# ProPrj___2024-03-13_07-09-23_2025-06-12.net
KiCad netlist of a schematic drawn in EasyEDA Pro
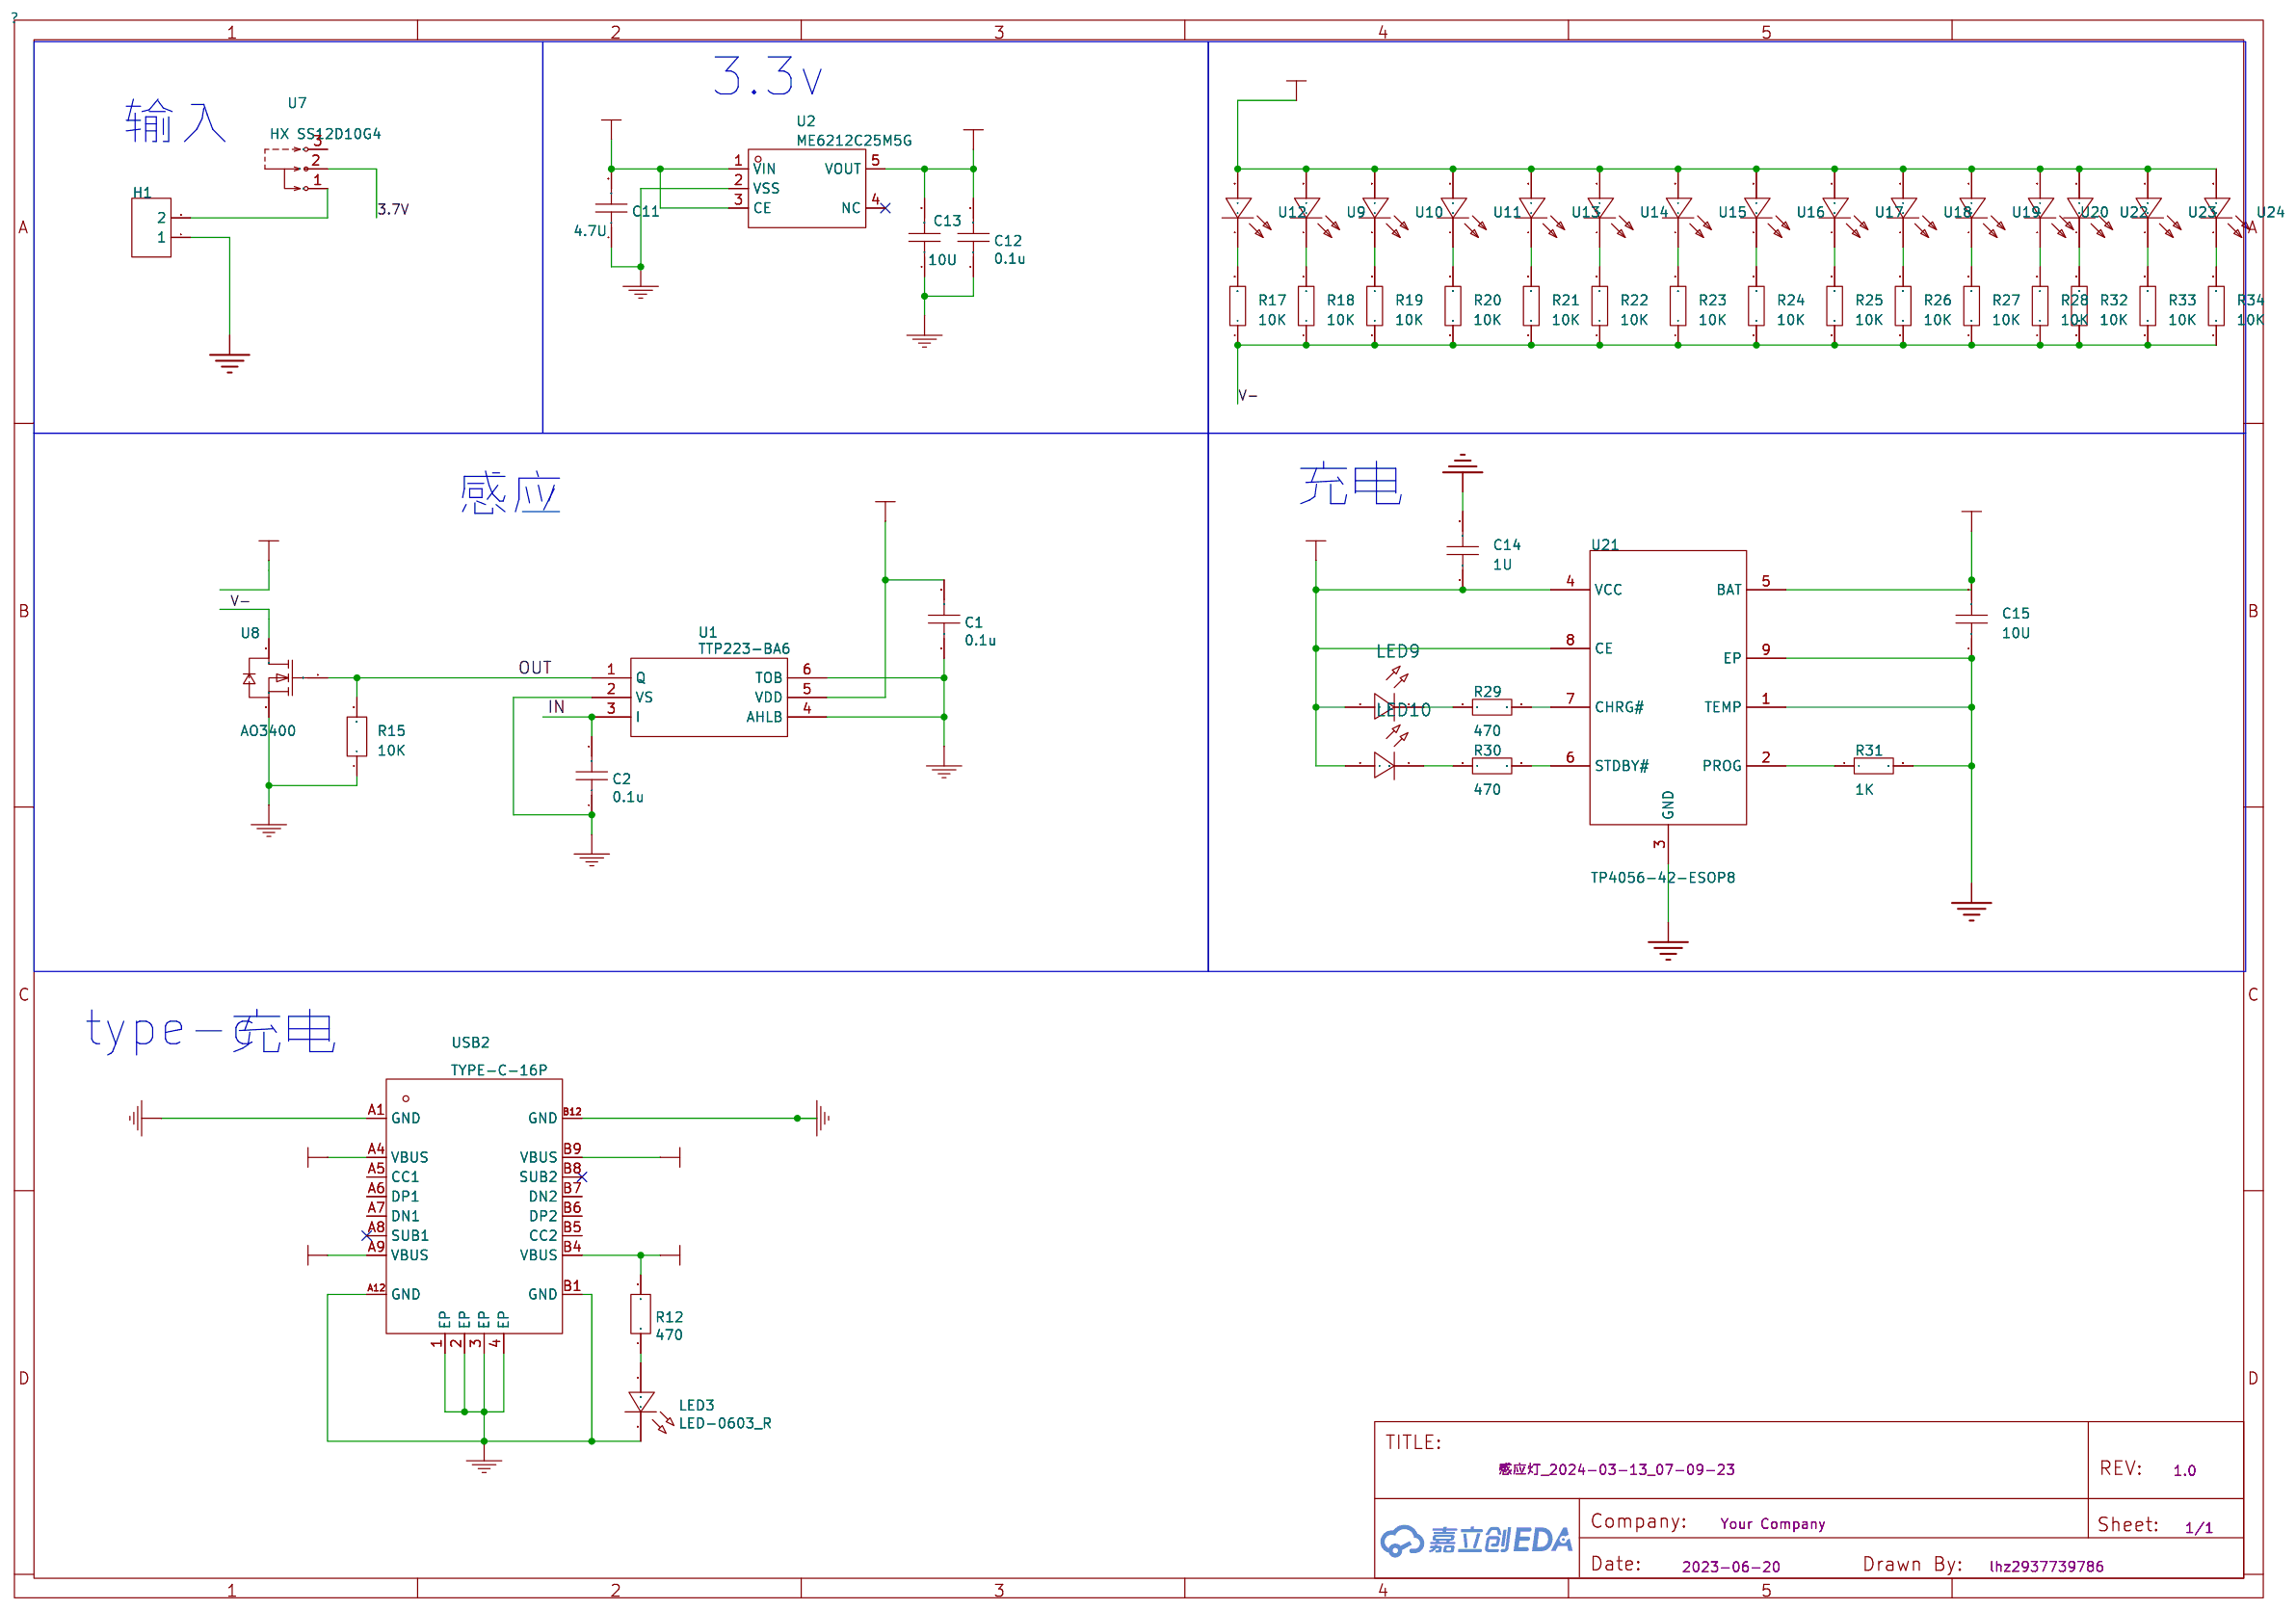
[diagram p0: schematic sheet]

(export (version "E")
  (design (tool "Eeschema 10.0.6"))
  (components
    (comp (ref "C1")
      (value "0.1u")
      (footprint "easyedapro:footprint_1e94")
      (libsource (lib "easyedapro") (part "0.1u"))
    )
    (comp (ref "C2")
      (value "0.1u")
      (footprint "easyedapro:footprint_1e94")
      (libsource (lib "easyedapro") (part "0.1u"))
    )
    (comp (ref "C11")
      (value "4.7U")
      (footprint "easyedapro:footprint_d063")
      (libsource (lib "easyedapro") (part "4.7U"))
    )
    (comp (ref "C12")
      (value "0.1u")
      (footprint "easyedapro:footprint_d063")
      (libsource (lib "easyedapro") (part "0.1u"))
    )
    (comp (ref "C13")
      (value "10U")
      (footprint "easyedapro:footprint_d063")
      (libsource (lib "easyedapro") (part "10U"))
    )
    (comp (ref "C14")
      (value "1U")
      (footprint "easyedapro:C0603")
      (libsource (lib "easyedapro") (part "CapAcitance"))
    )
    (comp (ref "C15")
      (value "10U")
      (footprint "easyedapro:C0603")
      (libsource (lib "easyedapro") (part "CapAcitance"))
    )
    (comp (ref "H1")
      (value "~")
      (footprint "easyedapro:HDR-TH_2P-P2.54-V-F")
      (libsource (lib "easyedapro") (part "Header-Female-2.54_1x2"))
    )
    (comp (ref "LED3")
      (value "LED-0603_R")
      (footprint "easyedapro:footprint_1210")
      (fields
        (field (name "Manufacturer Part") "19-217/R6C-AL1M2VY/3T")
        (field (name "Manufacturer") "EVERLIGHT(台湾亿光)")
      )
      (libsource (lib "easyedapro") (part "LED-0603_R"))
    )
    (comp (ref "LED9")
      (value "~")
      (footprint "easyedapro:LED_0603")
      (libsource (lib "easyedapro") (part "LED_R"))
    )
    (comp (ref "LED10")
      (value "~")
      (footprint "easyedapro:LED_0603")
      (libsource (lib "easyedapro") (part "LED_R"))
    )
    (comp (ref "R12")
      (value "470")
      (footprint "easyedapro:footprint_1dde")
      (libsource (lib "easyedapro") (part "470"))
    )
    (comp (ref "R15")
      (value "10K")
      (footprint "easyedapro:footprint_4dfc")
      (libsource (lib "easyedapro") (part "10K"))
    )
    (comp (ref "R17") (value "10K") (footprint "easyedapro:R0805") (libsource (lib "easyedapro") (part "电阻")))
    (comp (ref "R18") (value "10K") (footprint "easyedapro:R0805") (libsource (lib "easyedapro") (part "电阻")))
    (comp (ref "R19") (value "10K") (footprint "easyedapro:R0805") (libsource (lib "easyedapro") (part "电阻")))
    (comp (ref "R20") (value "10K") (footprint "easyedapro:R0805") (libsource (lib "easyedapro") (part "电阻")))
    (comp (ref "R21") (value "10K") (footprint "easyedapro:R0805") (libsource (lib "easyedapro") (part "电阻")))
    (comp (ref "R22") (value "10K") (footprint "easyedapro:R0805") (libsource (lib "easyedapro") (part "电阻")))
    (comp (ref "R23") (value "10K") (footprint "easyedapro:R0805") (libsource (lib "easyedapro") (part "电阻")))
    (comp (ref "R24") (value "10K") (footprint "easyedapro:R0805") (libsource (lib "easyedapro") (part "电阻")))
    (comp (ref "R25") (value "10K") (footprint "easyedapro:R0805") (libsource (lib "easyedapro") (part "电阻")))
    (comp (ref "R26") (value "10K") (footprint "easyedapro:R0805") (libsource (lib "easyedapro") (part "电阻")))
    (comp (ref "R27") (value "10K") (footprint "easyedapro:R0805") (libsource (lib "easyedapro") (part "电阻")))
    (comp (ref "R28") (value "10K") (footprint "easyedapro:R0805") (libsource (lib "easyedapro") (part "电阻")))
    (comp (ref "R29") (value "470") (footprint "easyedapro:R0805") (libsource (lib "easyedapro") (part "电阻")))
    (comp (ref "R30") (value "470") (footprint "easyedapro:R0805") (libsource (lib "easyedapro") (part "电阻")))
    (comp (ref "R31") (value "1K") (footprint "easyedapro:R0805") (libsource (lib "easyedapro") (part "电阻")))
    (comp (ref "R32") (value "10K") (footprint "easyedapro:R0805") (libsource (lib "easyedapro") (part "电阻")))
    (comp (ref "R33") (value "10K") (footprint "easyedapro:R0805") (libsource (lib "easyedapro") (part "电阻")))
    (comp (ref "R34") (value "10K") (footprint "easyedapro:R0805") (libsource (lib "easyedapro") (part "电阻")))
    (comp (ref "U1")
      (value "TTP223-BA6")
      (footprint "easyedapro:footprint_07fe")
      (libsource (lib "easyedapro") (part "TTP223-BA6"))
    )
    (comp (ref "U2")
      (value "ME6212C25M5G")
      (footprint "easyedapro:footprint_203e")
      (fields (field (name "Manufacturer") "MICRONE(南京微盟)"))
      (libsource (lib "easyedapro") (part "ME6212C25M5G"))
    )
    (comp (ref "U7")
      (value "HX SS12D10G4")
      (footprint "easyedapro:footprint_a0a6")
      (fields (field (name "Manufacturer") "hanxia(韩下)"))
      (libsource (lib "easyedapro") (part "HX SS12D10G4"))
    )
    (comp (ref "U8")
      (value "AO3400")
      (footprint "easyedapro:footprint_8e82")
      (fields (field (name "Manufacturer") "ElecSuper(静芯微）"))
      (libsource (lib "easyedapro") (part "AO3400"))
    )
    (comp (ref "U9")
      (value "~")
      (footprint "easyedapro:led-smd_l3.5-w2.8-r-fd-white")
      (fields (field (name "Manufacturer Part") "LED2835"))
      (libsource (lib "easyedapro") (part "led2835"))
    )
    (comp (ref "U10")
      (value "~")
      (footprint "easyedapro:led-smd_l3.5-w2.8-r-fd-white")
      (fields (field (name "Manufacturer Part") "LED2835"))
      (libsource (lib "easyedapro") (part "led2835"))
    )
    (comp (ref "U11")
      (value "~")
      (footprint "easyedapro:led-smd_l3.5-w2.8-r-fd-white")
      (fields (field (name "Manufacturer Part") "LED2835"))
      (libsource (lib "easyedapro") (part "led2835"))
    )
    (comp (ref "U12")
      (value "~")
      (footprint "easyedapro:led-smd_l3.5-w2.8-r-fd-white")
      (fields (field (name "Manufacturer Part") "LED2835"))
      (libsource (lib "easyedapro") (part "led2835"))
    )
    (comp (ref "U13")
      (value "~")
      (footprint "easyedapro:led-smd_l3.5-w2.8-r-fd-white")
      (fields (field (name "Manufacturer Part") "LED2835"))
      (libsource (lib "easyedapro") (part "led2835"))
    )
    (comp (ref "U14")
      (value "~")
      (footprint "easyedapro:led-smd_l3.5-w2.8-r-fd-white")
      (fields (field (name "Manufacturer Part") "LED2835"))
      (libsource (lib "easyedapro") (part "led2835"))
    )
    (comp (ref "U15")
      (value "~")
      (footprint "easyedapro:led-smd_l3.5-w2.8-r-fd-white")
      (fields (field (name "Manufacturer Part") "LED2835"))
      (libsource (lib "easyedapro") (part "led2835"))
    )
    (comp (ref "U16")
      (value "~")
      (footprint "easyedapro:led-smd_l3.5-w2.8-r-fd-white")
      (fields (field (name "Manufacturer Part") "LED2835"))
      (libsource (lib "easyedapro") (part "led2835"))
    )
    (comp (ref "U17")
      (value "~")
      (footprint "easyedapro:led-smd_l3.5-w2.8-r-fd-white")
      (fields (field (name "Manufacturer Part") "LED2835"))
      (libsource (lib "easyedapro") (part "led2835"))
    )
    (comp (ref "U18")
      (value "~")
      (footprint "easyedapro:led-smd_l3.5-w2.8-r-fd-white")
      (fields (field (name "Manufacturer Part") "LED2835"))
      (libsource (lib "easyedapro") (part "led2835"))
    )
    (comp (ref "U19")
      (value "~")
      (footprint "easyedapro:led-smd_l3.5-w2.8-r-fd-white")
      (fields (field (name "Manufacturer Part") "LED2835"))
      (libsource (lib "easyedapro") (part "led2835"))
    )
    (comp (ref "U20")
      (value "~")
      (footprint "easyedapro:led-smd_l3.5-w2.8-r-fd-white")
      (fields (field (name "Manufacturer Part") "LED2835"))
      (libsource (lib "easyedapro") (part "led2835"))
    )
    (comp (ref "U21")
      (value "TP4056-42-ESOP8")
      (footprint "easyedapro:ESOP-8_L4.9-W3.9-P1.27-LS6.0-BL-EP")
      (description "充电电池的类型:-;电池单元组数:-;最大充电电流:-;充满的电池组电压:-;最大供应电压:-;")
      (fields (field (name "Manufacturer") "TOPPOWER(南京拓微)"))
      (libsource (lib "easyedapro") (part "TP4056"))
    )
    (comp (ref "U22")
      (value "~")
      (footprint "easyedapro:led-smd_l3.5-w2.8-r-fd-white")
      (fields (field (name "Manufacturer Part") "LED2835"))
      (libsource (lib "easyedapro") (part "led2835"))
    )
    (comp (ref "U23")
      (value "~")
      (footprint "easyedapro:led-smd_l3.5-w2.8-r-fd-white")
      (fields (field (name "Manufacturer Part") "LED2835"))
      (libsource (lib "easyedapro") (part "led2835"))
    )
    (comp (ref "U24")
      (value "~")
      (footprint "easyedapro:led-smd_l3.5-w2.8-r-fd-white")
      (fields (field (name "Manufacturer Part") "LED2835"))
      (libsource (lib "easyedapro") (part "led2835"))
    )
    (comp (ref "USB2")
      (value "TYPE-C-16P")
      (footprint "easyedapro:footprint_feef")
      (fields
        (field (name "Manufacturer Part") "KH-TYPE-C-16P")
        (field (name "Manufacturer") "Shenzhen Kinghelm Elec")
      )
      (libsource (lib "easyedapro") (part "TYPE-C-16P"))
    )
  )
  (nets
    (net (code "1") (name "/IN") (class "Default")
      (node (ref "C2") (pin "2") (pinfunction "2_2") (pintype "unspecified"))
      (node (ref "U1") (pin "3") (pinfunction "I_3") (pintype "unspecified"))
    )
    (net (code "2") (name "/OUT") (class "Default")
      (node (ref "R15") (pin "2") (pinfunction "2_2") (pintype "unspecified"))
      (node (ref "U1") (pin "1") (pinfunction "Q_1") (pintype "unspecified"))
      (node (ref "U8") (pin "1") (pinfunction "G_1") (pintype "unspecified"))
    )
    (net (code "3") (name "/V-") (class "Default")
      (node (ref "R17") (pin "1") (pinfunction "1_1") (pintype "input"))
      (node (ref "R18") (pin "1") (pinfunction "1_1") (pintype "input"))
      (node (ref "R19") (pin "1") (pinfunction "1_1") (pintype "input"))
      (node (ref "R20") (pin "1") (pinfunction "1_1") (pintype "input"))
      (node (ref "R21") (pin "1") (pinfunction "1_1") (pintype "input"))
      (node (ref "R22") (pin "1") (pinfunction "1_1") (pintype "input"))
      (node (ref "R23") (pin "1") (pinfunction "1_1") (pintype "input"))
      (node (ref "R24") (pin "1") (pinfunction "1_1") (pintype "input"))
      (node (ref "R25") (pin "1") (pinfunction "1_1") (pintype "input"))
      (node (ref "R26") (pin "1") (pinfunction "1_1") (pintype "input"))
      (node (ref "R27") (pin "1") (pinfunction "1_1") (pintype "input"))
      (node (ref "R28") (pin "1") (pinfunction "1_1") (pintype "input"))
      (node (ref "R32") (pin "1") (pinfunction "1_1") (pintype "input"))
      (node (ref "R33") (pin "1") (pinfunction "1_1") (pintype "input"))
      (node (ref "R34") (pin "1") (pinfunction "1_1") (pintype "input"))
      (node (ref "U8") (pin "3") (pinfunction "D_3") (pintype "unspecified"))
    )
    (net (code "4") (name "3.3V") (class "Default")
      (node (ref "C1") (pin "2") (pinfunction "2_2") (pintype "unspecified"))
      (node (ref "C12") (pin "2") (pinfunction "2_2") (pintype "unspecified"))
      (node (ref "C13") (pin "2") (pinfunction "2_2") (pintype "unspecified"))
      (node (ref "U1") (pin "5") (pinfunction "VDD_5") (pintype "unspecified"))
      (node (ref "U2") (pin "5") (pinfunction "VOUT_5") (pintype "unspecified"))
    )
    (net (code "5") (name "3.7V") (class "Default")
      (node (ref "C11") (pin "2") (pinfunction "2_2") (pintype "unspecified"))
      (node (ref "C15") (pin "2") (pinfunction "2_2") (pintype "input"))
      (node (ref "U10") (pin "2") (pinfunction "A_2") (pintype "input"))
      (node (ref "U11") (pin "2") (pinfunction "A_2") (pintype "input"))
      (node (ref "U12") (pin "2") (pinfunction "A_2") (pintype "input"))
      (node (ref "U13") (pin "2") (pinfunction "A_2") (pintype "input"))
      (node (ref "U14") (pin "2") (pinfunction "A_2") (pintype "input"))
      (node (ref "U15") (pin "2") (pinfunction "A_2") (pintype "input"))
      (node (ref "U16") (pin "2") (pinfunction "A_2") (pintype "input"))
      (node (ref "U17") (pin "2") (pinfunction "A_2") (pintype "input"))
      (node (ref "U18") (pin "2") (pinfunction "A_2") (pintype "input"))
      (node (ref "U19") (pin "2") (pinfunction "A_2") (pintype "input"))
      (node (ref "U2") (pin "1") (pinfunction "VIN_1") (pintype "unspecified"))
      (node (ref "U2") (pin "3") (pinfunction "CE_3") (pintype "unspecified"))
      (node (ref "U20") (pin "2") (pinfunction "A_2") (pintype "input"))
      (node (ref "U21") (pin "5") (pinfunction "BAT_5") (pintype "input"))
      (node (ref "U22") (pin "2") (pinfunction "A_2") (pintype "input"))
      (node (ref "U23") (pin "2") (pinfunction "A_2") (pintype "input"))
      (node (ref "U24") (pin "2") (pinfunction "A_2") (pintype "input"))
      (node (ref "U7") (pin "2") (pinfunction "2_2") (pintype "unspecified"))
      (node (ref "U9") (pin "2") (pinfunction "A_2") (pintype "input"))
    )
    (net (code "6") (name "5V") (class "Default")
      (node (ref "C14") (pin "1") (pinfunction "1_1") (pintype "input"))
      (node (ref "LED10") (pin "2") (pinfunction "A_2") (pintype "input"))
      (node (ref "LED9") (pin "2") (pinfunction "A_2") (pintype "input"))
      (node (ref "R12") (pin "2") (pinfunction "2_2") (pintype "unspecified"))
      (node (ref "U21") (pin "4") (pinfunction "VCC_4") (pintype "input"))
      (node (ref "U21") (pin "8") (pinfunction "CE_8") (pintype "input"))
      (node (ref "USB2") (pin "A4") (pinfunction "VBUS_A4") (pintype "unspecified"))
      (node (ref "USB2") (pin "A9") (pinfunction "VBUS_A9") (pintype "unspecified"))
      (node (ref "USB2") (pin "B4") (pinfunction "VBUS_B4") (pintype "unspecified"))
      (node (ref "USB2") (pin "B9") (pinfunction "VBUS_B9") (pintype "unspecified"))
    )
    (net (code "7") (name "GND") (class "Default")
      (node (ref "C1") (pin "1") (pinfunction "1_1") (pintype "unspecified"))
      (node (ref "C11") (pin "1") (pinfunction "1_1") (pintype "unspecified"))
      (node (ref "C12") (pin "1") (pinfunction "1_1") (pintype "unspecified"))
      (node (ref "C13") (pin "1") (pinfunction "1_1") (pintype "unspecified"))
      (node (ref "C14") (pin "2") (pinfunction "2_2") (pintype "input"))
      (node (ref "C15") (pin "1") (pinfunction "1_1") (pintype "input"))
      (node (ref "C2") (pin "1") (pinfunction "1_1") (pintype "unspecified"))
      (node (ref "H1") (pin "1") (pinfunction "1_1") (pintype "input"))
      (node (ref "LED3") (pin "2") (pinfunction "2_2") (pintype "unspecified"))
      (node (ref "R15") (pin "1") (pinfunction "1_1") (pintype "unspecified"))
      (node (ref "R31") (pin "2") (pinfunction "2_2") (pintype "input"))
      (node (ref "U1") (pin "2") (pinfunction "VS_2") (pintype "unspecified"))
      (node (ref "U1") (pin "4") (pinfunction "AHLB_4") (pintype "unspecified"))
      (node (ref "U1") (pin "6") (pinfunction "TOB_6") (pintype "unspecified"))
      (node (ref "U2") (pin "2") (pinfunction "VSS_2") (pintype "unspecified"))
      (node (ref "U21") (pin "1") (pinfunction "TEMP_1") (pintype "input"))
      (node (ref "U21") (pin "3") (pinfunction "GND_3") (pintype "input"))
      (node (ref "U21") (pin "9") (pinfunction "EP_9") (pintype "input"))
      (node (ref "U8") (pin "2") (pinfunction "S_2") (pintype "unspecified"))
      (node (ref "USB2") (pin "1") (pinfunction "EP_1") (pintype "unspecified"))
      (node (ref "USB2") (pin "2") (pinfunction "EP_2") (pintype "unspecified"))
      (node (ref "USB2") (pin "3") (pinfunction "EP_3") (pintype "unspecified"))
      (node (ref "USB2") (pin "4") (pinfunction "EP_4") (pintype "unspecified"))
      (node (ref "USB2") (pin "A1") (pinfunction "GND_A1") (pintype "unspecified"))
      (node (ref "USB2") (pin "A12") (pinfunction "GND_A12") (pintype "unspecified"))
      (node (ref "USB2") (pin "B1") (pinfunction "GND_B1") (pintype "unspecified"))
      (node (ref "USB2") (pin "B12") (pinfunction "GND_B12") (pintype "unspecified"))
    )
    (net (code "8") (name "Net-(H1-Pad2)") (class "Default")
      (node (ref "H1") (pin "2") (pinfunction "2_2") (pintype "input"))
      (node (ref "U7") (pin "1") (pinfunction "1_1") (pintype "unspecified"))
    )
    (net (code "9") (name "Net-(LED3-Pad1)") (class "Default")
      (node (ref "LED3") (pin "1") (pinfunction "1_1") (pintype "unspecified"))
      (node (ref "R12") (pin "1") (pinfunction "1_1") (pintype "unspecified"))
    )
    (net (code "10") (name "Net-(LED9-C)") (class "Default")
      (node (ref "LED9") (pin "1") (pinfunction "C_1") (pintype "input"))
      (node (ref "R29") (pin "1") (pinfunction "1_1") (pintype "input"))
    )
    (net (code "11") (name "Net-(LED10-C)") (class "Default")
      (node (ref "LED10") (pin "1") (pinfunction "C_1") (pintype "input"))
      (node (ref "R30") (pin "1") (pinfunction "1_1") (pintype "input"))
    )
    (net (code "12") (name "Net-(U9-K)") (class "Default")
      (node (ref "R18") (pin "2") (pinfunction "2_2") (pintype "input"))
      (node (ref "U9") (pin "1") (pinfunction "K_1") (pintype "input"))
    )
    (net (code "13") (name "Net-(U10-K)") (class "Default")
      (node (ref "R19") (pin "2") (pinfunction "2_2") (pintype "input"))
      (node (ref "U10") (pin "1") (pinfunction "K_1") (pintype "input"))
    )
    (net (code "14") (name "Net-(U11-K)") (class "Default")
      (node (ref "R20") (pin "2") (pinfunction "2_2") (pintype "input"))
      (node (ref "U11") (pin "1") (pinfunction "K_1") (pintype "input"))
    )
    (net (code "15") (name "Net-(U12-K)") (class "Default")
      (node (ref "R17") (pin "2") (pinfunction "2_2") (pintype "input"))
      (node (ref "U12") (pin "1") (pinfunction "K_1") (pintype "input"))
    )
    (net (code "16") (name "Net-(U13-K)") (class "Default")
      (node (ref "R21") (pin "2") (pinfunction "2_2") (pintype "input"))
      (node (ref "U13") (pin "1") (pinfunction "K_1") (pintype "input"))
    )
    (net (code "17") (name "Net-(U14-K)") (class "Default")
      (node (ref "R22") (pin "2") (pinfunction "2_2") (pintype "input"))
      (node (ref "U14") (pin "1") (pinfunction "K_1") (pintype "input"))
    )
    (net (code "18") (name "Net-(U15-K)") (class "Default")
      (node (ref "R23") (pin "2") (pinfunction "2_2") (pintype "input"))
      (node (ref "U15") (pin "1") (pinfunction "K_1") (pintype "input"))
    )
    (net (code "19") (name "Net-(U16-K)") (class "Default")
      (node (ref "R24") (pin "2") (pinfunction "2_2") (pintype "input"))
      (node (ref "U16") (pin "1") (pinfunction "K_1") (pintype "input"))
    )
    (net (code "20") (name "Net-(U17-K)") (class "Default")
      (node (ref "R25") (pin "2") (pinfunction "2_2") (pintype "input"))
      (node (ref "U17") (pin "1") (pinfunction "K_1") (pintype "input"))
    )
    (net (code "21") (name "Net-(U18-K)") (class "Default")
      (node (ref "R26") (pin "2") (pinfunction "2_2") (pintype "input"))
      (node (ref "U18") (pin "1") (pinfunction "K_1") (pintype "input"))
    )
    (net (code "22") (name "Net-(U19-K)") (class "Default")
      (node (ref "R27") (pin "2") (pinfunction "2_2") (pintype "input"))
      (node (ref "U19") (pin "1") (pinfunction "K_1") (pintype "input"))
    )
    (net (code "23") (name "Net-(U20-K)") (class "Default")
      (node (ref "R28") (pin "2") (pinfunction "2_2") (pintype "input"))
      (node (ref "U20") (pin "1") (pinfunction "K_1") (pintype "input"))
    )
    (net (code "24") (name "Net-(U21-CHRG#)") (class "Default")
      (node (ref "R29") (pin "2") (pinfunction "2_2") (pintype "input"))
      (node (ref "U21") (pin "7") (pinfunction "CHRG#_7") (pintype "input"))
    )
    (net (code "25") (name "Net-(U21-PROG)") (class "Default")
      (node (ref "R31") (pin "1") (pinfunction "1_1") (pintype "input"))
      (node (ref "U21") (pin "2") (pinfunction "PROG_2") (pintype "input"))
    )
    (net (code "26") (name "Net-(U21-STDBY#)") (class "Default")
      (node (ref "R30") (pin "2") (pinfunction "2_2") (pintype "input"))
      (node (ref "U21") (pin "6") (pinfunction "STDBY#_6") (pintype "input"))
    )
    (net (code "27") (name "Net-(U22-K)") (class "Default")
      (node (ref "R32") (pin "2") (pinfunction "2_2") (pintype "input"))
      (node (ref "U22") (pin "1") (pinfunction "K_1") (pintype "input"))
    )
    (net (code "28") (name "Net-(U23-K)") (class "Default")
      (node (ref "R33") (pin "2") (pinfunction "2_2") (pintype "input"))
      (node (ref "U23") (pin "1") (pinfunction "K_1") (pintype "input"))
    )
    (net (code "29") (name "Net-(U24-K)") (class "Default")
      (node (ref "R34") (pin "2") (pinfunction "2_2") (pintype "input"))
      (node (ref "U24") (pin "1") (pinfunction "K_1") (pintype "input"))
    )
    (net (code "30") (name "unconnected-(U2-NC-Pad4)") (class "Default")
      (node (ref "U2") (pin "4") (pinfunction "NC_4") (pintype "unspecified+no_connect"))
    )
    (net (code "31") (name "unconnected-(U7-Pad3)") (class "Default")
      (node (ref "U7") (pin "3") (pinfunction "3_3") (pintype "unspecified"))
    )
    (net (code "32") (name "unconnected-(USB2-CC1-PadA5)") (class "Default")
      (node (ref "USB2") (pin "A5") (pinfunction "CC1_A5") (pintype "unspecified"))
    )
    (net (code "33") (name "unconnected-(USB2-CC2-PadB5)") (class "Default")
      (node (ref "USB2") (pin "B5") (pinfunction "CC2_B5") (pintype "unspecified"))
    )
    (net (code "34") (name "unconnected-(USB2-DN1-PadA7)") (class "Default")
      (node (ref "USB2") (pin "A7") (pinfunction "DN1_A7") (pintype "unspecified"))
    )
    (net (code "35") (name "unconnected-(USB2-DN2-PadB7)") (class "Default")
      (node (ref "USB2") (pin "B7") (pinfunction "DN2_B7") (pintype "unspecified"))
    )
    (net (code "36") (name "unconnected-(USB2-DP1-PadA6)") (class "Default")
      (node (ref "USB2") (pin "A6") (pinfunction "DP1_A6") (pintype "unspecified"))
    )
    (net (code "37") (name "unconnected-(USB2-DP2-PadB6)") (class "Default")
      (node (ref "USB2") (pin "B6") (pinfunction "DP2_B6") (pintype "unspecified"))
    )
    (net (code "38") (name "unconnected-(USB2-SUB1-PadA8)") (class "Default")
      (node (ref "USB2") (pin "A8") (pinfunction "SUB1_A8") (pintype "unspecified+no_connect"))
    )
    (net (code "39") (name "unconnected-(USB2-SUB2-PadB8)") (class "Default")
      (node (ref "USB2") (pin "B8") (pinfunction "SUB2_B8") (pintype "unspecified+no_connect"))
    )
  )
)
